# USB_UART.net
KiCad netlist of a schematic drawn in Altium Designer
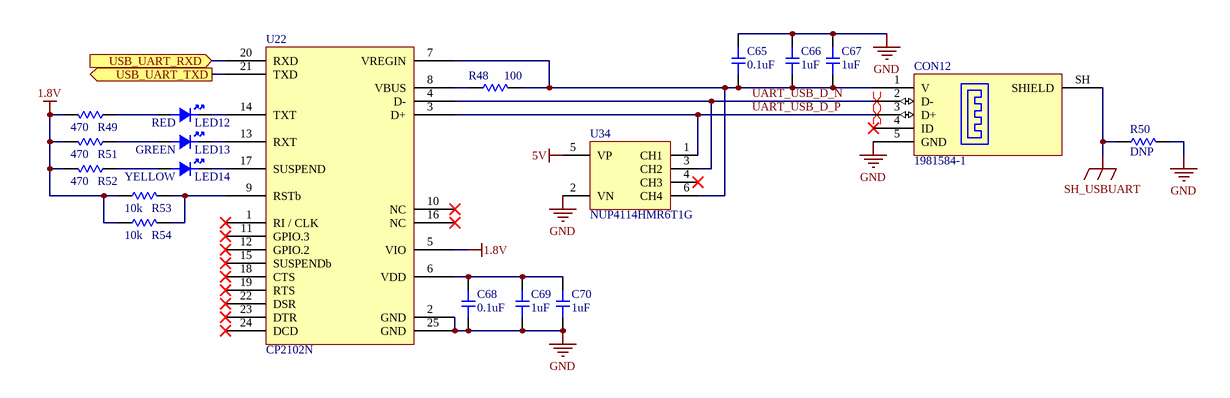
[diagram p0: USB_UART.SchDoc]

(export (version "E")
  (design (tool "Eeschema 10.0.6"))
  (components
    (comp (ref "C65")
      (value "0.1uF")
      (footprint "0603-CAP")
      (description "Capacitor")
      (libsource (lib "AMDC") (part "Capacitor"))
    )
    (comp (ref "C66")
      (value "1uF")
      (footprint "0603-CAP")
      (description "Capacitor")
      (libsource (lib "AMDC") (part "Capacitor"))
    )
    (comp (ref "C67")
      (value "1uF")
      (footprint "0603-CAP")
      (description "Capacitor")
      (libsource (lib "AMDC") (part "Capacitor"))
    )
    (comp (ref "C68")
      (value "0.1uF")
      (footprint "0603-CAP")
      (description "Capacitor")
      (libsource (lib "AMDC") (part "Capacitor"))
    )
    (comp (ref "C69")
      (value "1uF")
      (footprint "0603-CAP")
      (description "Capacitor")
      (libsource (lib "AMDC") (part "Capacitor"))
    )
    (comp (ref "C70")
      (value "1uF")
      (footprint "0603-CAP")
      (description "Capacitor")
      (libsource (lib "AMDC") (part "Capacitor"))
    )
    (comp (ref "CON12")
      (value "1981584-1")
      (footprint "1981584-1")
      (description "CONN RCPT MICRO USB TYPE AB")
      (libsource (lib "AMDC") (part "1981584-1"))
    )
    (comp (ref "LED12")
      (value "RED")
      (footprint "0603-LED")
      (fields (field (name "Comment") "LED"))
      (libsource (lib "AMDC") (part "LED"))
    )
    (comp (ref "LED13")
      (value "GREEN")
      (footprint "0603-LED")
      (fields (field (name "Comment") "LED"))
      (libsource (lib "AMDC") (part "LED"))
    )
    (comp (ref "LED14")
      (value "YELLOW")
      (footprint "0603-LED")
      (fields (field (name "Comment") "LED"))
      (libsource (lib "AMDC") (part "LED"))
    )
    (comp (ref "R48")
      (value "100")
      (footprint "0603-RES")
      (description "Resistor")
      (libsource (lib "AMDC") (part "Resistor"))
    )
    (comp (ref "R49")
      (value "470")
      (footprint "0603-RES")
      (description "Resistor")
      (libsource (lib "AMDC") (part "Resistor"))
    )
    (comp (ref "R50")
      (value "DNP")
      (footprint "0603-RES")
      (description "Resistor")
      (libsource (lib "AMDC") (part "Resistor"))
    )
    (comp (ref "R51")
      (value "470")
      (footprint "0603-RES")
      (description "Resistor")
      (libsource (lib "AMDC") (part "Resistor"))
    )
    (comp (ref "R52")
      (value "470")
      (footprint "0603-RES")
      (description "Resistor")
      (libsource (lib "AMDC") (part "Resistor"))
    )
    (comp (ref "R53")
      (value "10k")
      (footprint "0603-RES")
      (description "Resistor")
      (libsource (lib "AMDC") (part "Resistor"))
    )
    (comp (ref "R54")
      (value "10k")
      (footprint "0603-RES")
      (description "Resistor")
      (libsource (lib "AMDC") (part "Resistor"))
    )
    (comp (ref "U22")
      (value "CP2102N")
      (footprint "QFN50P400X400X80_HS-25N")
      (description "IC USB TO UART BRIDGE QFN24")
      (libsource (lib "AMDC") (part "CP2102N"))
    )
    (comp (ref "U34")
      (value "NUP4114HMR6T1G")
      (footprint "TSOP95P280X110-6N")
      (description "TVS DIODE 5.5V 10V 6TSOP")
      (libsource (lib "AMDC") (part "NUP4114HMR6T1G"))
    )
  )
  (nets
    (net (code "1") (name "/UART_USB_D_N") (class "Default")
      (node (ref "CON12") (pin "2") (pinfunction "D-_2") (pintype "bidirectional"))
      (node (ref "U22") (pin "4") (pinfunction "D-_4") (pintype "passive"))
      (node (ref "U34") (pin "3") (pinfunction "CH2_3") (pintype "passive"))
    )
    (net (code "2") (name "/UART_USB_D_P") (class "Default")
      (node (ref "CON12") (pin "3") (pinfunction "D+_3") (pintype "bidirectional"))
      (node (ref "U22") (pin "3") (pinfunction "D+_3") (pintype "passive"))
      (node (ref "U34") (pin "1") (pinfunction "CH1_1") (pintype "passive"))
    )
    (net (code "3") (name "/USB_UART_RXD") (class "Default")
      (node (ref "U22") (pin "20") (pinfunction "RXD_20") (pintype "passive"))
    )
    (net (code "4") (name "/USB_UART_TXD") (class "Default")
      (node (ref "U22") (pin "21") (pinfunction "TXD_21") (pintype "passive"))
    )
    (net (code "5") (name "1.8V") (class "Default")
      (node (ref "R49") (pin "2") (pinfunction "2_2") (pintype "passive"))
      (node (ref "R51") (pin "2") (pinfunction "2_2") (pintype "passive"))
      (node (ref "R52") (pin "2") (pinfunction "2_2") (pintype "passive"))
      (node (ref "R53") (pin "1") (pinfunction "1_1") (pintype "passive"))
      (node (ref "R54") (pin "1") (pinfunction "1_1") (pintype "passive"))
      (node (ref "U22") (pin "5") (pinfunction "VIO_5") (pintype "passive"))
    )
    (net (code "6") (name "5V") (class "Default")
      (node (ref "U34") (pin "5") (pinfunction "VP_5") (pintype "passive"))
    )
    (net (code "7") (name "GND") (class "Default")
      (node (ref "C65") (pin "2") (pinfunction "2_2") (pintype "passive"))
      (node (ref "C66") (pin "2") (pinfunction "2_2") (pintype "passive"))
      (node (ref "C67") (pin "2") (pinfunction "2_2") (pintype "passive"))
      (node (ref "C68") (pin "1") (pinfunction "1_1") (pintype "passive"))
      (node (ref "C69") (pin "1") (pinfunction "1_1") (pintype "passive"))
      (node (ref "C70") (pin "1") (pinfunction "1_1") (pintype "passive"))
      (node (ref "CON12") (pin "5") (pinfunction "GND_5") (pintype "passive"))
      (node (ref "R50") (pin "2") (pinfunction "2_2") (pintype "passive"))
      (node (ref "U22") (pin "2") (pinfunction "GND_2") (pintype "passive"))
      (node (ref "U22") (pin "25") (pinfunction "GND_25") (pintype "passive"))
      (node (ref "U34") (pin "2") (pinfunction "VN_2") (pintype "passive"))
    )
    (net (code "8") (name "Net-(CON12-V)") (class "Default")
      (node (ref "C65") (pin "1") (pinfunction "1_1") (pintype "passive"))
      (node (ref "C66") (pin "1") (pinfunction "1_1") (pintype "passive"))
      (node (ref "C67") (pin "1") (pinfunction "1_1") (pintype "passive"))
      (node (ref "CON12") (pin "1") (pinfunction "V_1") (pintype "passive"))
      (node (ref "R48") (pin "2") (pinfunction "2_2") (pintype "passive"))
      (node (ref "U22") (pin "7") (pinfunction "VREGIN_7") (pintype "passive"))
      (node (ref "U34") (pin "6") (pinfunction "CH4_6") (pintype "passive"))
    )
    (net (code "9") (name "Net-(LED12-PadA)") (class "Default")
      (node (ref "LED12") (pin "A") (pinfunction "A_A") (pintype "passive"))
      (node (ref "R49") (pin "1") (pinfunction "1_1") (pintype "passive"))
    )
    (net (code "10") (name "Net-(LED13-PadA)") (class "Default")
      (node (ref "LED13") (pin "A") (pinfunction "A_A") (pintype "passive"))
      (node (ref "R51") (pin "1") (pinfunction "1_1") (pintype "passive"))
    )
    (net (code "11") (name "Net-(LED14-PadA)") (class "Default")
      (node (ref "LED14") (pin "A") (pinfunction "A_A") (pintype "passive"))
      (node (ref "R52") (pin "1") (pinfunction "1_1") (pintype "passive"))
    )
    (net (code "12") (name "Net-(U22-RSTb)") (class "Default")
      (node (ref "R53") (pin "2") (pinfunction "2_2") (pintype "passive"))
      (node (ref "R54") (pin "2") (pinfunction "2_2") (pintype "passive"))
      (node (ref "U22") (pin "9") (pinfunction "RSTb_9") (pintype "passive"))
    )
    (net (code "13") (name "Net-(U22-RXT)") (class "Default")
      (node (ref "LED13") (pin "C") (pinfunction "C_C") (pintype "passive"))
      (node (ref "U22") (pin "13") (pinfunction "RXT_13") (pintype "passive"))
    )
    (net (code "14") (name "Net-(U22-SUSPEND)") (class "Default")
      (node (ref "LED14") (pin "C") (pinfunction "C_C") (pintype "passive"))
      (node (ref "U22") (pin "17") (pinfunction "SUSPEND_17") (pintype "passive"))
    )
    (net (code "15") (name "Net-(U22-TXT)") (class "Default")
      (node (ref "LED12") (pin "C") (pinfunction "C_C") (pintype "passive"))
      (node (ref "U22") (pin "14") (pinfunction "TXT_14") (pintype "passive"))
    )
    (net (code "16") (name "Net-(U22-VBUS)") (class "Default")
      (node (ref "R48") (pin "1") (pinfunction "1_1") (pintype "passive"))
      (node (ref "U22") (pin "8") (pinfunction "VBUS_8") (pintype "passive"))
    )
    (net (code "17") (name "Net-(U22-VDD)") (class "Default")
      (node (ref "C68") (pin "2") (pinfunction "2_2") (pintype "passive"))
      (node (ref "C69") (pin "2") (pinfunction "2_2") (pintype "passive"))
      (node (ref "C70") (pin "2") (pinfunction "2_2") (pintype "passive"))
      (node (ref "U22") (pin "6") (pinfunction "VDD_6") (pintype "passive"))
    )
    (net (code "18") (name "SH_USBUART") (class "Default")
      (node (ref "CON12") (pin "SH") (pinfunction "SHIELD_SH") (pintype "passive"))
      (node (ref "R50") (pin "1") (pinfunction "1_1") (pintype "passive"))
    )
    (net (code "19") (name "unconnected-(CON12-ID-Pad4)") (class "Default")
      (node (ref "CON12") (pin "4") (pinfunction "ID_4") (pintype "passive+no_connect"))
    )
    (net (code "20") (name "unconnected-(U22-CTS-Pad18)") (class "Default")
      (node (ref "U22") (pin "18") (pinfunction "CTS_18") (pintype "passive+no_connect"))
    )
    (net (code "21") (name "unconnected-(U22-DCD-Pad24)") (class "Default")
      (node (ref "U22") (pin "24") (pinfunction "DCD_24") (pintype "passive+no_connect"))
    )
    (net (code "22") (name "unconnected-(U22-DSR-Pad22)") (class "Default")
      (node (ref "U22") (pin "22") (pinfunction "DSR_22") (pintype "passive+no_connect"))
    )
    (net (code "23") (name "unconnected-(U22-DTR-Pad23)") (class "Default")
      (node (ref "U22") (pin "23") (pinfunction "DTR_23") (pintype "passive+no_connect"))
    )
    (net (code "24") (name "unconnected-(U22-GPIO.2-Pad12)") (class "Default")
      (node (ref "U22") (pin "12") (pinfunction "GPIO.2_12") (pintype "passive+no_connect"))
    )
    (net (code "25") (name "unconnected-(U22-GPIO.3-Pad11)") (class "Default")
      (node (ref "U22") (pin "11") (pinfunction "GPIO.3_11") (pintype "passive+no_connect"))
    )
    (net (code "26") (name "unconnected-(U22-NC-Pad10)") (class "Default")
      (node (ref "U22") (pin "10") (pinfunction "NC_10") (pintype "passive+no_connect"))
    )
    (net (code "27") (name "unconnected-(U22-NC-Pad16)") (class "Default")
      (node (ref "U22") (pin "16") (pinfunction "NC_16") (pintype "passive+no_connect"))
    )
    (net (code "28") (name "unconnected-(U22-RI_{slash}_CLK-Pad1)") (class "Default")
      (node (ref "U22") (pin "1") (pinfunction "RI_/_CLK_1") (pintype "passive+no_connect"))
    )
    (net (code "29") (name "unconnected-(U22-RTS-Pad19)") (class "Default")
      (node (ref "U22") (pin "19") (pinfunction "RTS_19") (pintype "passive+no_connect"))
    )
    (net (code "30") (name "unconnected-(U22-SUSPENDb-Pad15)") (class "Default")
      (node (ref "U22") (pin "15") (pinfunction "SUSPENDb_15") (pintype "passive+no_connect"))
    )
    (net (code "31") (name "unconnected-(U34-CH3-Pad4)") (class "Default")
      (node (ref "U34") (pin "4") (pinfunction "CH3_4") (pintype "passive+no_connect"))
    )
  )
)
